# FXAS21002_gyro.net
KiCad netlist of a schematic drawn in EAGLE
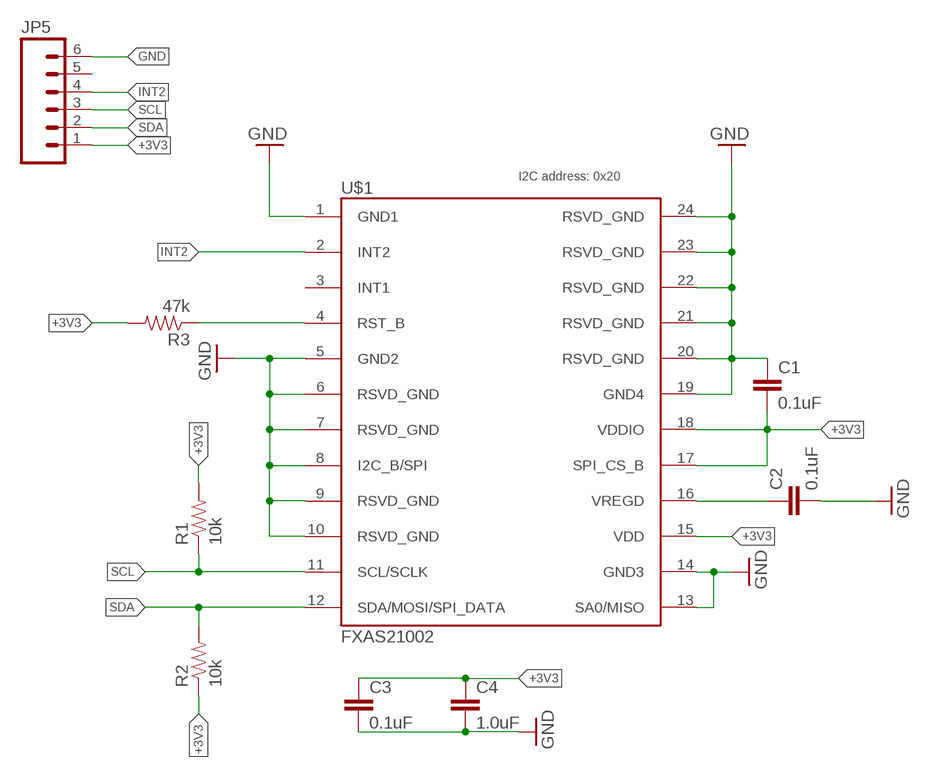
[diagram p0: schematic, sheet 1]

(export (version "E")
  (design (tool "Eeschema 10.0.6"))
  (components
    (comp (ref "C1")
      (value "0.1uF")
      (footprint "eagle-import:0805")
      (libsource (lib "eagle-import") (part "CAP0805"))
    )
    (comp (ref "C2")
      (value "0.1uF")
      (footprint "eagle-import:0805")
      (libsource (lib "eagle-import") (part "CAP0805"))
    )
    (comp (ref "C3")
      (value "0.1uF")
      (footprint "eagle-import:0805")
      (libsource (lib "eagle-import") (part "CAP0805"))
    )
    (comp (ref "C4")
      (value "1.0uF")
      (footprint "eagle-import:0805")
      (libsource (lib "eagle-import") (part "CAP0805"))
    )
    (comp (ref "JP5")
      (value "M06SIP")
      (footprint "eagle-import:1X06")
      (libsource (lib "eagle-import") (part "M06SIP"))
    )
    (comp (ref "R1")
      (value "10k")
      (footprint "eagle-import:0805")
      (libsource (lib "eagle-import") (part "RESISTOR0805-RES"))
    )
    (comp (ref "R2")
      (value "10k")
      (footprint "eagle-import:0805")
      (libsource (lib "eagle-import") (part "RESISTOR0805-RES"))
    )
    (comp (ref "R3")
      (value "47k")
      (footprint "eagle-import:0805")
      (libsource (lib "eagle-import") (part "RESISTOR0805-RES"))
    )
    (comp (ref "U$1")
      (value "FXAS21002")
      (footprint "eagle-import:24QFN")
      (libsource (lib "eagle-import") (part "FXAS21002"))
    )
  )
  (nets
    (net (code "1") (name "+3V3") (class "Default")
      (node (ref "C1") (pin "2") (pinfunction "2_2") (pintype "passive"))
      (node (ref "C3") (pin "1") (pinfunction "1_1") (pintype "passive"))
      (node (ref "C4") (pin "1") (pinfunction "1_1") (pintype "passive"))
      (node (ref "JP5") (pin "1") (pinfunction "1_1") (pintype "passive"))
      (node (ref "R1") (pin "2") (pinfunction "2_2") (pintype "passive"))
      (node (ref "R2") (pin "1") (pinfunction "1_1") (pintype "passive"))
      (node (ref "R3") (pin "2") (pinfunction "2_2") (pintype "passive"))
      (node (ref "U$1") (pin "15") (pinfunction "VDD_15") (pintype "bidirectional"))
      (node (ref "U$1") (pin "17") (pinfunction "SPI_CS_B_17") (pintype "bidirectional"))
      (node (ref "U$1") (pin "18") (pinfunction "VDDIO_18") (pintype "bidirectional"))
    )
    (net (code "2") (name "GND") (class "Default")
      (node (ref "C1") (pin "1") (pinfunction "1_1") (pintype "passive"))
      (node (ref "C2") (pin "2") (pinfunction "2_2") (pintype "passive"))
      (node (ref "C3") (pin "2") (pinfunction "2_2") (pintype "passive"))
      (node (ref "C4") (pin "2") (pinfunction "2_2") (pintype "passive"))
      (node (ref "JP5") (pin "6") (pinfunction "6_6") (pintype "passive"))
      (node (ref "U$1") (pin "1") (pinfunction "GND1_1") (pintype "bidirectional"))
      (node (ref "U$1") (pin "10") (pinfunction "RSVD_GND_10") (pintype "bidirectional"))
      (node (ref "U$1") (pin "13") (pinfunction "SA0/MISO_13") (pintype "bidirectional"))
      (node (ref "U$1") (pin "14") (pinfunction "GND3_14") (pintype "bidirectional"))
      (node (ref "U$1") (pin "19") (pinfunction "GND4_19") (pintype "bidirectional"))
      (node (ref "U$1") (pin "20") (pinfunction "RSVD_GND_20") (pintype "bidirectional"))
      (node (ref "U$1") (pin "21") (pinfunction "RSVD_GND_21") (pintype "bidirectional"))
      (node (ref "U$1") (pin "22") (pinfunction "RSVD_GND_22") (pintype "bidirectional"))
      (node (ref "U$1") (pin "23") (pinfunction "RSVD_GND_23") (pintype "bidirectional"))
      (node (ref "U$1") (pin "24") (pinfunction "RSVD_GND_24") (pintype "bidirectional"))
      (node (ref "U$1") (pin "5") (pinfunction "GND2_5") (pintype "bidirectional"))
      (node (ref "U$1") (pin "6") (pinfunction "RSVD_GND_6") (pintype "bidirectional"))
      (node (ref "U$1") (pin "7") (pinfunction "RSVD_GND_7") (pintype "bidirectional"))
      (node (ref "U$1") (pin "8") (pinfunction "I2C_B/SPI_8") (pintype "bidirectional"))
      (node (ref "U$1") (pin "9") (pinfunction "RSVD_GND_9") (pintype "bidirectional"))
    )
    (net (code "3") (name "INT2") (class "Default")
      (node (ref "JP5") (pin "4") (pinfunction "4_4") (pintype "passive"))
      (node (ref "U$1") (pin "2") (pinfunction "INT2_2") (pintype "bidirectional"))
    )
    (net (code "4") (name "Net-(U$1-RST_B)") (class "Default")
      (node (ref "R3") (pin "1") (pinfunction "1_1") (pintype "passive"))
      (node (ref "U$1") (pin "4") (pinfunction "RST_B_4") (pintype "bidirectional"))
    )
    (net (code "5") (name "Net-(U$1-VREGD)") (class "Default")
      (node (ref "C2") (pin "1") (pinfunction "1_1") (pintype "passive"))
      (node (ref "U$1") (pin "16") (pinfunction "VREGD_16") (pintype "bidirectional"))
    )
    (net (code "6") (name "SCL") (class "Default")
      (node (ref "JP5") (pin "3") (pinfunction "3_3") (pintype "passive"))
      (node (ref "R1") (pin "1") (pinfunction "1_1") (pintype "passive"))
      (node (ref "U$1") (pin "11") (pinfunction "SCL/SCLK_11") (pintype "bidirectional"))
    )
    (net (code "7") (name "SDA") (class "Default")
      (node (ref "JP5") (pin "2") (pinfunction "2_2") (pintype "passive"))
      (node (ref "R2") (pin "2") (pinfunction "2_2") (pintype "passive"))
      (node (ref "U$1") (pin "12") (pinfunction "SDA/MOSI/SPI_DATA_12") (pintype "bidirectional"))
    )
    (net (code "8") (name "unconnected-(JP5-Pad5)") (class "Default")
      (node (ref "JP5") (pin "5") (pinfunction "5_5") (pintype "passive"))
    )
    (net (code "9") (name "unconnected-(U$1-INT1-Pad3)") (class "Default")
      (node (ref "U$1") (pin "3") (pinfunction "INT1_3") (pintype "bidirectional"))
    )
  )
)
